# Ak_ll__Lamba.net
KiCad netlist of a schematic drawn in EAGLE
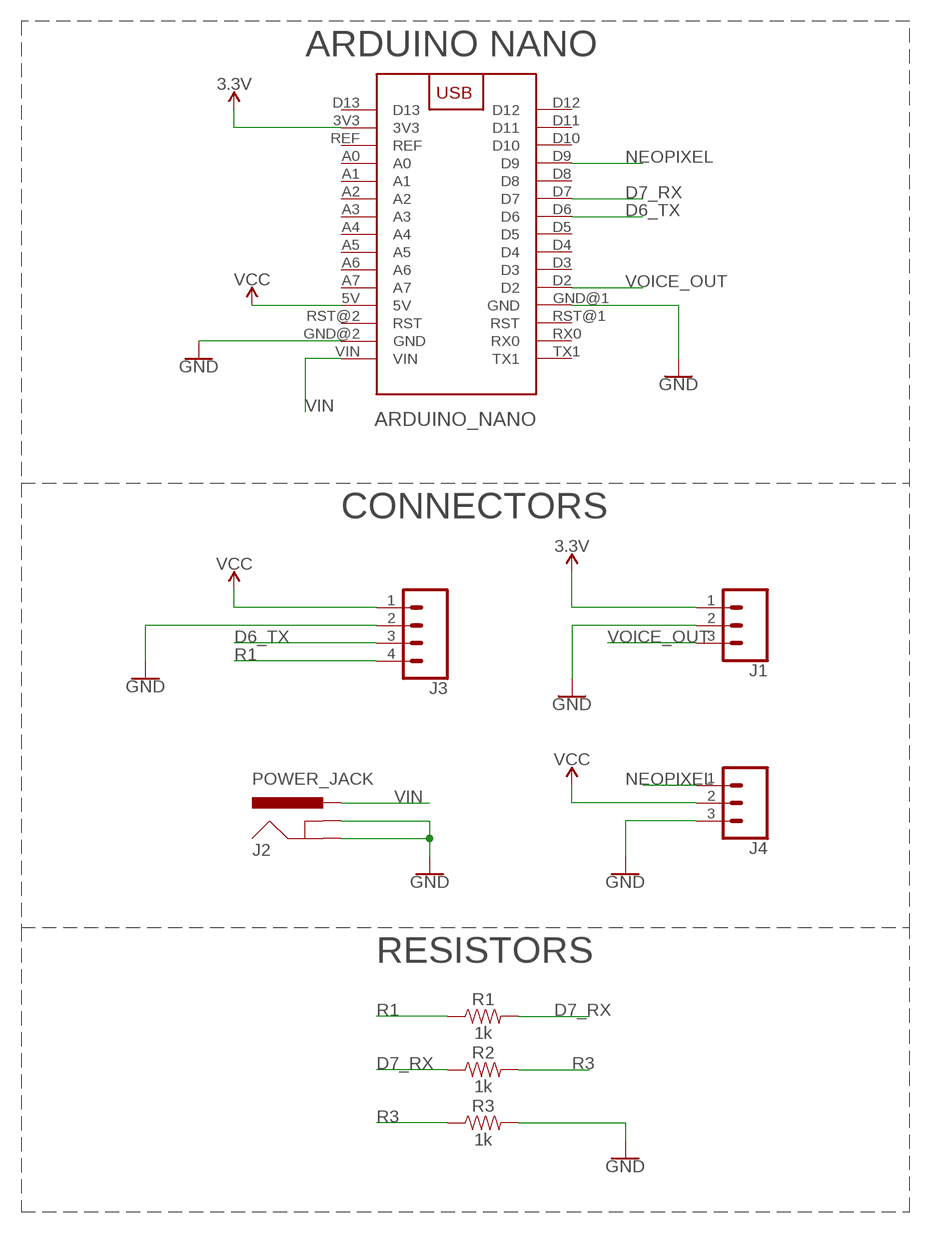
[diagram p0: schematic, sheet 1]

(export (version "E")
  (design (tool "Eeschema 10.0.6"))
  (components
    (comp (ref "ARDUINO_NANO")
      (value "ARDUINONANO")
      (footprint "eagle-import:ARDUINONANO")
      (libsource (lib "eagle-import") (part "ARDUINONANO"))
    )
    (comp (ref "J1")
      (value "455-1750-1-ND")
      (footprint "eagle-import:1X03")
      (libsource (lib "eagle-import") (part "CONN_03"))
    )
    (comp (ref "J2")
      (value "POWER_JACK")
      (footprint "eagle-import:POWER_JACK_PTH")
      (libsource (lib "eagle-import") (part "POWER_JACK"))
    )
    (comp (ref "J3")
      (value "CONN_04PTH")
      (footprint "eagle-import:1X04")
      (libsource (lib "eagle-import") (part "CONN_04PTH"))
    )
    (comp (ref "J4")
      (value "455-1750-1-ND")
      (footprint "eagle-import:1X03")
      (libsource (lib "eagle-import") (part "CONN_03"))
    )
    (comp (ref "R1")
      (value "1k")
      (footprint "eagle-import:AXIAL-0.3")
      (libsource (lib "eagle-import") (part "1KOHM-HORIZ-1/4W-5%"))
    )
    (comp (ref "R2")
      (value "1k")
      (footprint "eagle-import:AXIAL-0.3")
      (libsource (lib "eagle-import") (part "1KOHM-HORIZ-1/4W-5%"))
    )
    (comp (ref "R3")
      (value "1k")
      (footprint "eagle-import:AXIAL-0.3")
      (libsource (lib "eagle-import") (part "1KOHM-HORIZ-1/4W-5%"))
    )
  )
  (nets
    (net (code "1") (name "/D6_TX") (class "Default")
      (node (ref "ARDUINO_NANO") (pin "D6") (pinfunction "D6_D6") (pintype "bidirectional"))
      (node (ref "J3") (pin "3") (pinfunction "3_3") (pintype "passive"))
    )
    (net (code "2") (name "/D7_RX") (class "Default")
      (node (ref "ARDUINO_NANO") (pin "D7") (pinfunction "D7_D7") (pintype "bidirectional"))
      (node (ref "R1") (pin "P$2") (pinfunction "2_P$2") (pintype "passive"))
      (node (ref "R2") (pin "P$1") (pinfunction "1_P$1") (pintype "passive"))
    )
    (net (code "3") (name "/NEOPIXEL") (class "Default")
      (node (ref "ARDUINO_NANO") (pin "D9") (pinfunction "D9_D9") (pintype "bidirectional"))
      (node (ref "J4") (pin "1") (pinfunction "1_1") (pintype "passive"))
    )
    (net (code "4") (name "/R1") (class "Default")
      (node (ref "J3") (pin "4") (pinfunction "4_4") (pintype "passive"))
      (node (ref "R1") (pin "P$1") (pinfunction "1_P$1") (pintype "passive"))
    )
    (net (code "5") (name "/R3") (class "Default")
      (node (ref "R2") (pin "P$2") (pinfunction "2_P$2") (pintype "passive"))
      (node (ref "R3") (pin "P$1") (pinfunction "1_P$1") (pintype "passive"))
    )
    (net (code "6") (name "/VIN") (class "Default")
      (node (ref "ARDUINO_NANO") (pin "VIN") (pinfunction "VIN_VIN") (pintype "bidirectional"))
      (node (ref "J2") (pin "PWR") (pinfunction "PWR_PWR") (pintype "bidirectional"))
    )
    (net (code "7") (name "/VOICE_OUT") (class "Default")
      (node (ref "ARDUINO_NANO") (pin "D2") (pinfunction "D2_D2") (pintype "bidirectional"))
      (node (ref "J1") (pin "3") (pinfunction "3_3") (pintype "passive"))
    )
    (net (code "8") (name "3.3V") (class "Default")
      (node (ref "ARDUINO_NANO") (pin "3V3") (pinfunction "3V3_3V3") (pintype "bidirectional"))
      (node (ref "J1") (pin "1") (pinfunction "1_1") (pintype "passive"))
    )
    (net (code "9") (name "GND") (class "Default")
      (node (ref "ARDUINO_NANO") (pin "GND@1") (pinfunction "GND_GND@1") (pintype "bidirectional"))
      (node (ref "ARDUINO_NANO") (pin "GND@2") (pinfunction "GND_GND@2") (pintype "bidirectional"))
      (node (ref "J1") (pin "2") (pinfunction "2_2") (pintype "passive"))
      (node (ref "J2") (pin "GND") (pinfunction "GND_GND") (pintype "bidirectional"))
      (node (ref "J2") (pin "GNDBREAK") (pinfunction "GNDBREAK_GNDBREAK") (pintype "bidirectional"))
      (node (ref "J3") (pin "2") (pinfunction "2_2") (pintype "passive"))
      (node (ref "J4") (pin "3") (pinfunction "3_3") (pintype "passive"))
      (node (ref "R3") (pin "P$2") (pinfunction "2_P$2") (pintype "passive"))
    )
    (net (code "10") (name "VCC") (class "Default")
      (node (ref "ARDUINO_NANO") (pin "5V") (pinfunction "5V_5V") (pintype "bidirectional"))
      (node (ref "J3") (pin "1") (pinfunction "1_1") (pintype "passive"))
      (node (ref "J4") (pin "2") (pinfunction "2_2") (pintype "passive"))
    )
    (net (code "11") (name "unconnected-(ARDUINO_NANO-PadA0)") (class "Default")
      (node (ref "ARDUINO_NANO") (pin "A0") (pinfunction "A0_A0") (pintype "bidirectional"))
    )
    (net (code "12") (name "unconnected-(ARDUINO_NANO-PadA1)") (class "Default")
      (node (ref "ARDUINO_NANO") (pin "A1") (pinfunction "A1_A1") (pintype "bidirectional"))
    )
    (net (code "13") (name "unconnected-(ARDUINO_NANO-PadA2)") (class "Default")
      (node (ref "ARDUINO_NANO") (pin "A2") (pinfunction "A2_A2") (pintype "bidirectional"))
    )
    (net (code "14") (name "unconnected-(ARDUINO_NANO-PadA3)") (class "Default")
      (node (ref "ARDUINO_NANO") (pin "A3") (pinfunction "A3_A3") (pintype "bidirectional"))
    )
    (net (code "15") (name "unconnected-(ARDUINO_NANO-PadA4)") (class "Default")
      (node (ref "ARDUINO_NANO") (pin "A4") (pinfunction "A4_A4") (pintype "bidirectional"))
    )
    (net (code "16") (name "unconnected-(ARDUINO_NANO-PadA5)") (class "Default")
      (node (ref "ARDUINO_NANO") (pin "A5") (pinfunction "A5_A5") (pintype "bidirectional"))
    )
    (net (code "17") (name "unconnected-(ARDUINO_NANO-PadA6)") (class "Default")
      (node (ref "ARDUINO_NANO") (pin "A6") (pinfunction "A6_A6") (pintype "bidirectional"))
    )
    (net (code "18") (name "unconnected-(ARDUINO_NANO-PadA7)") (class "Default")
      (node (ref "ARDUINO_NANO") (pin "A7") (pinfunction "A7_A7") (pintype "bidirectional"))
    )
    (net (code "19") (name "unconnected-(ARDUINO_NANO-PadD3)") (class "Default")
      (node (ref "ARDUINO_NANO") (pin "D3") (pinfunction "D3_D3") (pintype "bidirectional"))
    )
    (net (code "20") (name "unconnected-(ARDUINO_NANO-PadD4)") (class "Default")
      (node (ref "ARDUINO_NANO") (pin "D4") (pinfunction "D4_D4") (pintype "bidirectional"))
    )
    (net (code "21") (name "unconnected-(ARDUINO_NANO-PadD5)") (class "Default")
      (node (ref "ARDUINO_NANO") (pin "D5") (pinfunction "D5_D5") (pintype "bidirectional"))
    )
    (net (code "22") (name "unconnected-(ARDUINO_NANO-PadD8)") (class "Default")
      (node (ref "ARDUINO_NANO") (pin "D8") (pinfunction "D8_D8") (pintype "bidirectional"))
    )
    (net (code "23") (name "unconnected-(ARDUINO_NANO-PadD10)") (class "Default")
      (node (ref "ARDUINO_NANO") (pin "D10") (pinfunction "D10_D10") (pintype "bidirectional"))
    )
    (net (code "24") (name "unconnected-(ARDUINO_NANO-PadD11)") (class "Default")
      (node (ref "ARDUINO_NANO") (pin "D11") (pinfunction "D11_D11") (pintype "bidirectional"))
    )
    (net (code "25") (name "unconnected-(ARDUINO_NANO-PadD12)") (class "Default")
      (node (ref "ARDUINO_NANO") (pin "D12") (pinfunction "D12_D12") (pintype "bidirectional"))
    )
    (net (code "26") (name "unconnected-(ARDUINO_NANO-PadD13)") (class "Default")
      (node (ref "ARDUINO_NANO") (pin "D13") (pinfunction "D13_D13") (pintype "bidirectional"))
    )
    (net (code "27") (name "unconnected-(ARDUINO_NANO-PadREF)") (class "Default")
      (node (ref "ARDUINO_NANO") (pin "REF") (pinfunction "REF_REF") (pintype "bidirectional"))
    )
    (net (code "28") (name "unconnected-(ARDUINO_NANO-PadRX0)") (class "Default")
      (node (ref "ARDUINO_NANO") (pin "RX0") (pinfunction "RX0_RX0") (pintype "bidirectional"))
    )
    (net (code "29") (name "unconnected-(ARDUINO_NANO-PadTX1)") (class "Default")
      (node (ref "ARDUINO_NANO") (pin "TX1") (pinfunction "TX1_TX1") (pintype "bidirectional"))
    )
    (net (code "30") (name "unconnected-(ARDUINO_NANO-RST-PadRST@1)") (class "Default")
      (node (ref "ARDUINO_NANO") (pin "RST@1") (pinfunction "RST_RST@1") (pintype "bidirectional"))
    )
    (net (code "31") (name "unconnected-(ARDUINO_NANO-RST-PadRST@2)") (class "Default")
      (node (ref "ARDUINO_NANO") (pin "RST@2") (pinfunction "RST_RST@2") (pintype "bidirectional"))
    )
  )
)
